# line_sensor.net
KiCad netlist of a schematic drawn in EAGLE
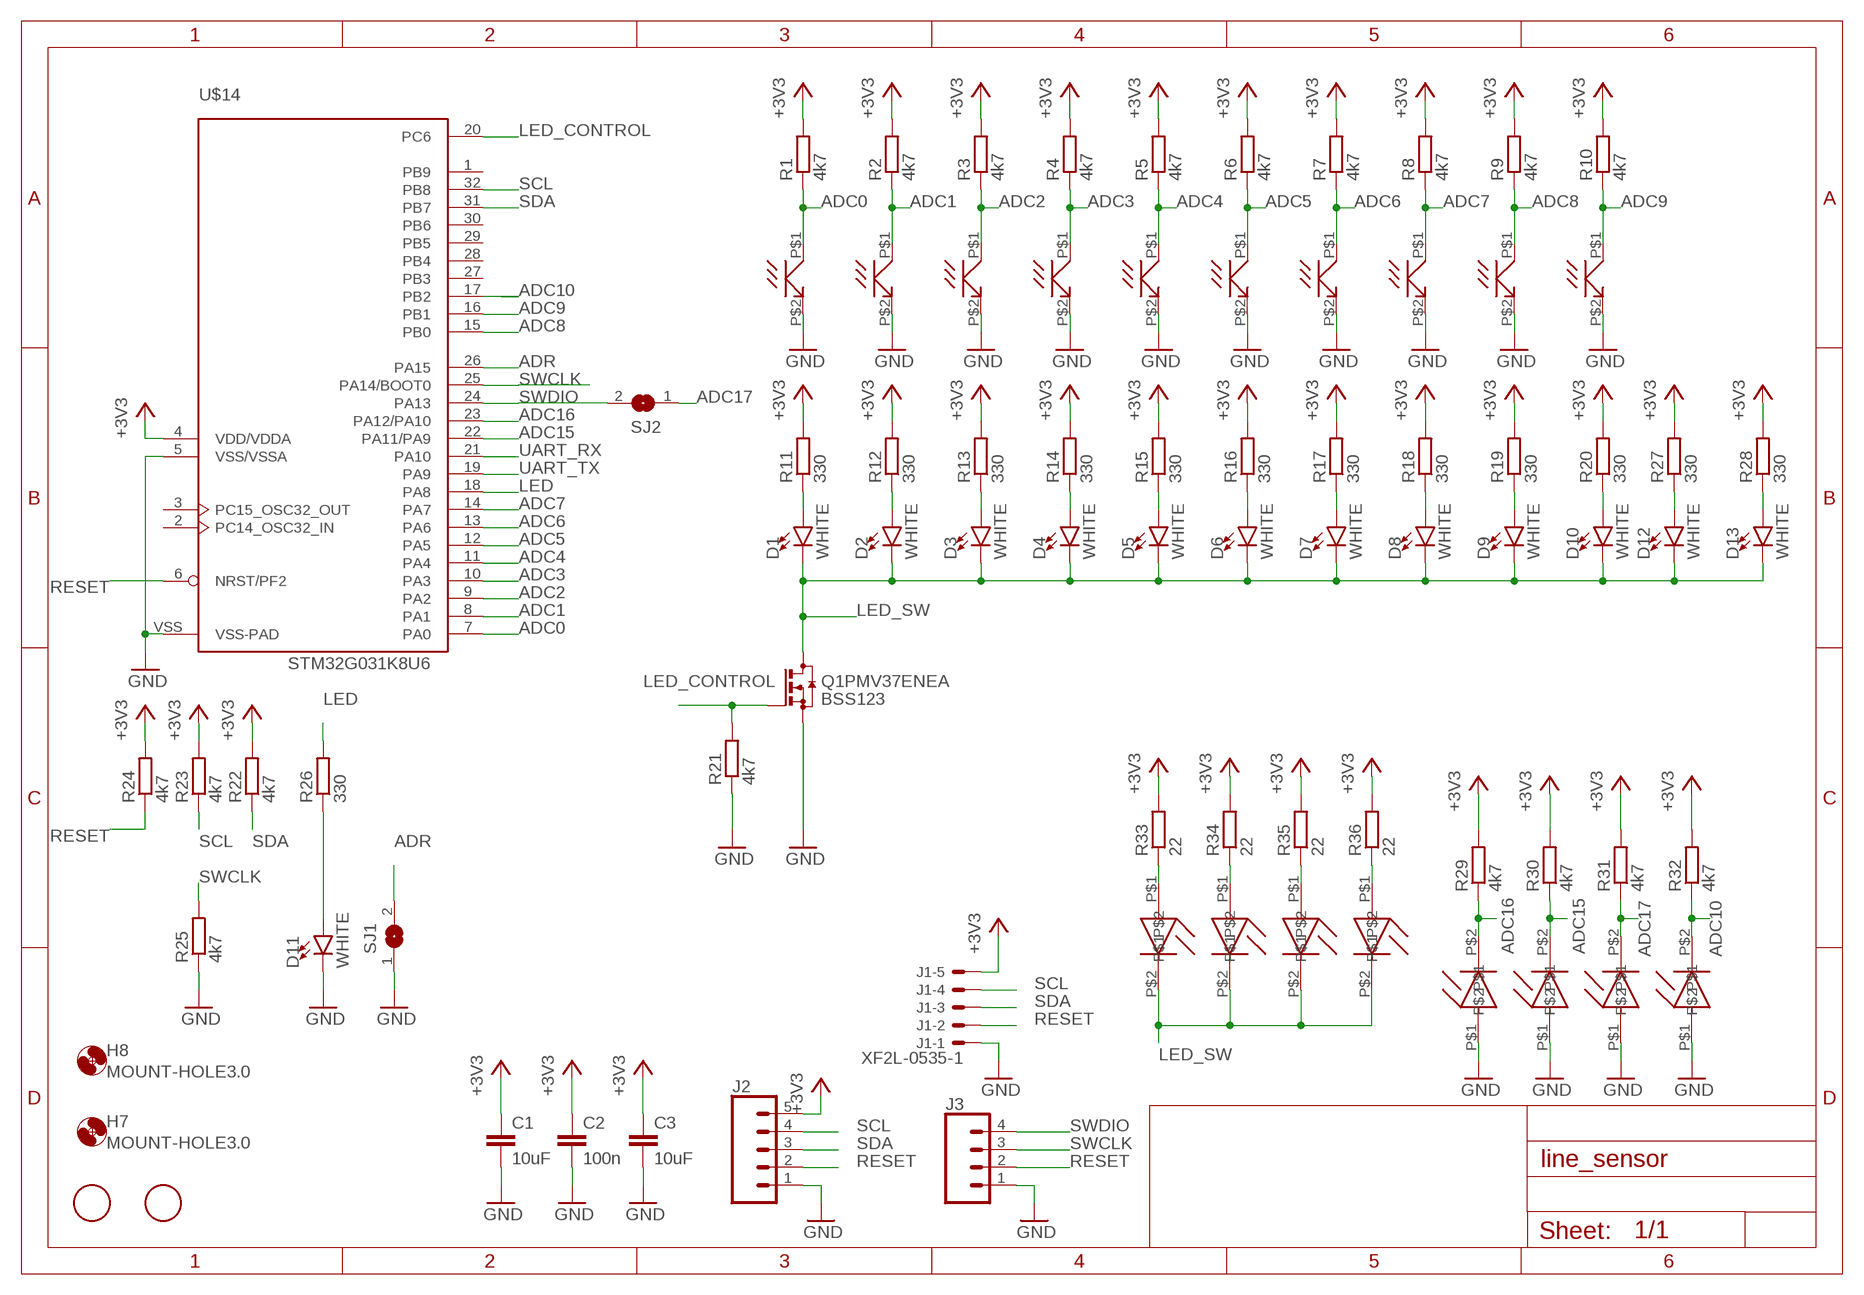
[diagram p0: schematic, sheet 1]

(export (version "E")
  (design (tool "Eeschema 10.0.6"))
  (components
    (comp (ref "C1")
      (value "10uF")
      (footprint "eagle-import:C0805K")
      (libsource (lib "eagle-import") (part "C-EUC0805K"))
    )
    (comp (ref "C2")
      (value "100n")
      (footprint "eagle-import:C0805K")
      (libsource (lib "eagle-import") (part "C-EUC0805K"))
    )
    (comp (ref "C3")
      (value "10uF")
      (footprint "eagle-import:C0805K")
      (libsource (lib "eagle-import") (part "C-EUC0805K"))
    )
    (comp (ref "D1")
      (value "WHITE")
      (footprint "eagle-import:LED-1206")
      (libsource (lib "eagle-import") (part "LED-WHITE1206"))
    )
    (comp (ref "D2")
      (value "WHITE")
      (footprint "eagle-import:LED-1206")
      (libsource (lib "eagle-import") (part "LED-WHITE1206"))
    )
    (comp (ref "D3")
      (value "WHITE")
      (footprint "eagle-import:LED-1206")
      (libsource (lib "eagle-import") (part "LED-WHITE1206"))
    )
    (comp (ref "D4")
      (value "WHITE")
      (footprint "eagle-import:LED-1206")
      (libsource (lib "eagle-import") (part "LED-WHITE1206"))
    )
    (comp (ref "D5")
      (value "WHITE")
      (footprint "eagle-import:LED-1206")
      (libsource (lib "eagle-import") (part "LED-WHITE1206"))
    )
    (comp (ref "D6")
      (value "WHITE")
      (footprint "eagle-import:LED-1206")
      (libsource (lib "eagle-import") (part "LED-WHITE1206"))
    )
    (comp (ref "D7")
      (value "WHITE")
      (footprint "eagle-import:LED-1206")
      (libsource (lib "eagle-import") (part "LED-WHITE1206"))
    )
    (comp (ref "D8")
      (value "WHITE")
      (footprint "eagle-import:LED-1206")
      (libsource (lib "eagle-import") (part "LED-WHITE1206"))
    )
    (comp (ref "D9")
      (value "WHITE")
      (footprint "eagle-import:LED-1206")
      (libsource (lib "eagle-import") (part "LED-WHITE1206"))
    )
    (comp (ref "D10")
      (value "WHITE")
      (footprint "eagle-import:LED-1206")
      (libsource (lib "eagle-import") (part "LED-WHITE1206"))
    )
    (comp (ref "D11")
      (value "WHITE")
      (footprint "eagle-import:LED-1206")
      (libsource (lib "eagle-import") (part "LED-WHITE1206"))
    )
    (comp (ref "D12")
      (value "WHITE")
      (footprint "eagle-import:LED-1206")
      (libsource (lib "eagle-import") (part "LED-WHITE1206"))
    )
    (comp (ref "D13")
      (value "WHITE")
      (footprint "eagle-import:LED-1206")
      (libsource (lib "eagle-import") (part "LED-WHITE1206"))
    )
    (comp (ref "H7")
      (value "MOUNT-HOLE3.0")
      (footprint "eagle-import:3,0")
      (libsource (lib "eagle-import") (part "MOUNT-HOLE3.0"))
    )
    (comp (ref "H8")
      (value "MOUNT-HOLE3.0")
      (footprint "eagle-import:3,0")
      (libsource (lib "eagle-import") (part "MOUNT-HOLE3.0"))
    )
    (comp (ref "J1")
      (value "XF2L-0535-1")
      (footprint "eagle-import:XF2L-0535-1")
      (fields (field (name "MPN") "XF2L-0535-1A"))
      (libsource (lib "eagle-import") (part "XF2-05?35-1L"))
    )
    (comp (ref "J2")
      (value "CONN_05")
      (footprint "eagle-import:1X05")
      (libsource (lib "eagle-import") (part "CONN_05"))
    )
    (comp (ref "J3")
      (value "CONN_04LOCK")
      (footprint "eagle-import:1X04_LOCK")
      (libsource (lib "eagle-import") (part "CONN_04LOCK"))
    )
    (comp (ref "Q1PMV37ENEA")
      (value "BSS123")
      (footprint "eagle-import:SOT23")
      (libsource (lib "eagle-import") (part "BSS123"))
    )
    (comp (ref "R1")
      (value "4k7")
      (footprint "eagle-import:M0805")
      (libsource (lib "eagle-import") (part "R-EU_M0805"))
    )
    (comp (ref "R2")
      (value "4k7")
      (footprint "eagle-import:M0805")
      (libsource (lib "eagle-import") (part "R-EU_M0805"))
    )
    (comp (ref "R3")
      (value "4k7")
      (footprint "eagle-import:M0805")
      (libsource (lib "eagle-import") (part "R-EU_M0805"))
    )
    (comp (ref "R4")
      (value "4k7")
      (footprint "eagle-import:M0805")
      (libsource (lib "eagle-import") (part "R-EU_M0805"))
    )
    (comp (ref "R5")
      (value "4k7")
      (footprint "eagle-import:M0805")
      (libsource (lib "eagle-import") (part "R-EU_M0805"))
    )
    (comp (ref "R6")
      (value "4k7")
      (footprint "eagle-import:M0805")
      (libsource (lib "eagle-import") (part "R-EU_M0805"))
    )
    (comp (ref "R7")
      (value "4k7")
      (footprint "eagle-import:M0805")
      (libsource (lib "eagle-import") (part "R-EU_M0805"))
    )
    (comp (ref "R8")
      (value "4k7")
      (footprint "eagle-import:M0805")
      (libsource (lib "eagle-import") (part "R-EU_M0805"))
    )
    (comp (ref "R9")
      (value "4k7")
      (footprint "eagle-import:M0805")
      (libsource (lib "eagle-import") (part "R-EU_M0805"))
    )
    (comp (ref "R10")
      (value "4k7")
      (footprint "eagle-import:M0805")
      (libsource (lib "eagle-import") (part "R-EU_M0805"))
    )
    (comp (ref "R11")
      (value "330")
      (footprint "eagle-import:M0805")
      (libsource (lib "eagle-import") (part "R-EU_M0805"))
    )
    (comp (ref "R12")
      (value "330")
      (footprint "eagle-import:M0805")
      (libsource (lib "eagle-import") (part "R-EU_M0805"))
    )
    (comp (ref "R13")
      (value "330")
      (footprint "eagle-import:M0805")
      (libsource (lib "eagle-import") (part "R-EU_M0805"))
    )
    (comp (ref "R14")
      (value "330")
      (footprint "eagle-import:M0805")
      (libsource (lib "eagle-import") (part "R-EU_M0805"))
    )
    (comp (ref "R15")
      (value "330")
      (footprint "eagle-import:M0805")
      (libsource (lib "eagle-import") (part "R-EU_M0805"))
    )
    (comp (ref "R16")
      (value "330")
      (footprint "eagle-import:M0805")
      (libsource (lib "eagle-import") (part "R-EU_M0805"))
    )
    (comp (ref "R17")
      (value "330")
      (footprint "eagle-import:M0805")
      (libsource (lib "eagle-import") (part "R-EU_M0805"))
    )
    (comp (ref "R18")
      (value "330")
      (footprint "eagle-import:M0805")
      (libsource (lib "eagle-import") (part "R-EU_M0805"))
    )
    (comp (ref "R19")
      (value "330")
      (footprint "eagle-import:M0805")
      (libsource (lib "eagle-import") (part "R-EU_M0805"))
    )
    (comp (ref "R20")
      (value "330")
      (footprint "eagle-import:M0805")
      (libsource (lib "eagle-import") (part "R-EU_M0805"))
    )
    (comp (ref "R21")
      (value "4k7")
      (footprint "eagle-import:M0805")
      (libsource (lib "eagle-import") (part "R-EU_M0805"))
    )
    (comp (ref "R22")
      (value "4k7")
      (footprint "eagle-import:M0805")
      (libsource (lib "eagle-import") (part "R-EU_M0805"))
    )
    (comp (ref "R23")
      (value "4k7")
      (footprint "eagle-import:M0805")
      (libsource (lib "eagle-import") (part "R-EU_M0805"))
    )
    (comp (ref "R24")
      (value "4k7")
      (footprint "eagle-import:M0805")
      (libsource (lib "eagle-import") (part "R-EU_M0805"))
    )
    (comp (ref "R25")
      (value "4k7")
      (footprint "eagle-import:M0805")
      (libsource (lib "eagle-import") (part "R-EU_M0805"))
    )
    (comp (ref "R26")
      (value "330")
      (footprint "eagle-import:M0805")
      (libsource (lib "eagle-import") (part "R-EU_M0805"))
    )
    (comp (ref "R27")
      (value "330")
      (footprint "eagle-import:M0805")
      (libsource (lib "eagle-import") (part "R-EU_M0805"))
    )
    (comp (ref "R28")
      (value "330")
      (footprint "eagle-import:M0805")
      (libsource (lib "eagle-import") (part "R-EU_M0805"))
    )
    (comp (ref "R29")
      (value "4k7")
      (footprint "eagle-import:M0805")
      (libsource (lib "eagle-import") (part "R-EU_M0805"))
    )
    (comp (ref "R30")
      (value "4k7")
      (footprint "eagle-import:M0805")
      (libsource (lib "eagle-import") (part "R-EU_M0805"))
    )
    (comp (ref "R31")
      (value "4k7")
      (footprint "eagle-import:M0805")
      (libsource (lib "eagle-import") (part "R-EU_M0805"))
    )
    (comp (ref "R32")
      (value "4k7")
      (footprint "eagle-import:M0805")
      (libsource (lib "eagle-import") (part "R-EU_M0805"))
    )
    (comp (ref "R33")
      (value "22")
      (footprint "eagle-import:M0805")
      (libsource (lib "eagle-import") (part "R-EU_M0805"))
    )
    (comp (ref "R34")
      (value "22")
      (footprint "eagle-import:M0805")
      (libsource (lib "eagle-import") (part "R-EU_M0805"))
    )
    (comp (ref "R35")
      (value "22")
      (footprint "eagle-import:M0805")
      (libsource (lib "eagle-import") (part "R-EU_M0805"))
    )
    (comp (ref "R36")
      (value "22")
      (footprint "eagle-import:M0805")
      (libsource (lib "eagle-import") (part "R-EU_M0805"))
    )
    (comp (ref "SJ1") (value "SJ") (footprint "eagle-import:SJ") (libsource (lib "eagle-import") (part "SJ")))
    (comp (ref "SJ2") (value "SJ") (footprint "eagle-import:SJ") (libsource (lib "eagle-import") (part "SJ")))
    (comp (ref "U$1")
      (value "SFH3710")
      (footprint "eagle-import:SFH710")
      (libsource (lib "eagle-import") (part "SFH3710"))
    )
    (comp (ref "U$2")
      (value "SFH3710")
      (footprint "eagle-import:SFH710")
      (libsource (lib "eagle-import") (part "SFH3710"))
    )
    (comp (ref "U$3")
      (value "SFH3710")
      (footprint "eagle-import:SFH710")
      (libsource (lib "eagle-import") (part "SFH3710"))
    )
    (comp (ref "U$4")
      (value "SFH3710")
      (footprint "eagle-import:SFH710")
      (libsource (lib "eagle-import") (part "SFH3710"))
    )
    (comp (ref "U$5")
      (value "SFH3710")
      (footprint "eagle-import:SFH710")
      (libsource (lib "eagle-import") (part "SFH3710"))
    )
    (comp (ref "U$6")
      (value "SFH3710")
      (footprint "eagle-import:SFH710")
      (libsource (lib "eagle-import") (part "SFH3710"))
    )
    (comp (ref "U$7")
      (value "SFH3710")
      (footprint "eagle-import:SFH710")
      (libsource (lib "eagle-import") (part "SFH3710"))
    )
    (comp (ref "U$8")
      (value "SFH3710")
      (footprint "eagle-import:SFH710")
      (libsource (lib "eagle-import") (part "SFH3710"))
    )
    (comp (ref "U$9")
      (value "SFH3710")
      (footprint "eagle-import:SFH710")
      (libsource (lib "eagle-import") (part "SFH3710"))
    )
    (comp (ref "U$10")
      (value "SFH3710")
      (footprint "eagle-import:SFH710")
      (libsource (lib "eagle-import") (part "SFH3710"))
    )
    (comp (ref "U$11")
      (value "LED_5MM_AXIAL")
      (footprint "eagle-import:LED_5MM_AXIAL")
      (libsource (lib "eagle-import") (part "LED_5MM_AXIAL"))
    )
    (comp (ref "U$12")
      (value "FIDUCIAL")
      (footprint "eagle-import:FIDUCIAL_1MM")
      (libsource (lib "eagle-import") (part "FIDUCIAL"))
    )
    (comp (ref "U$13")
      (value "FIDUCIAL")
      (footprint "eagle-import:FIDUCIAL_1MM")
      (libsource (lib "eagle-import") (part "FIDUCIAL"))
    )
    (comp (ref "U$14")
      (value "STM32G031K8U6")
      (footprint "eagle-import:UFQFPN32")
      (libsource (lib "eagle-import") (part "STM32G031K8U6"))
    )
    (comp (ref "U$15")
      (value "LED_5MM_AXIAL")
      (footprint "eagle-import:LED_5MM_AXIAL")
      (libsource (lib "eagle-import") (part "LED_5MM_AXIAL"))
    )
    (comp (ref "U$16")
      (value "LED_5MM_AXIAL")
      (footprint "eagle-import:LED_5MM_AXIAL")
      (libsource (lib "eagle-import") (part "LED_5MM_AXIAL"))
    )
    (comp (ref "U$17")
      (value "LED_5MM_AXIAL")
      (footprint "eagle-import:LED_5MM_AXIAL")
      (libsource (lib "eagle-import") (part "LED_5MM_AXIAL"))
    )
    (comp (ref "U$18")
      (value "LED_5MM_AXIAL")
      (footprint "eagle-import:LED_5MM_AXIAL")
      (libsource (lib "eagle-import") (part "LED_5MM_AXIAL"))
    )
    (comp (ref "U$19")
      (value "LED_5MM_AXIAL")
      (footprint "eagle-import:LED_5MM_AXIAL")
      (libsource (lib "eagle-import") (part "LED_5MM_AXIAL"))
    )
    (comp (ref "U$20")
      (value "LED_5MM_AXIAL")
      (footprint "eagle-import:LED_5MM_AXIAL")
      (libsource (lib "eagle-import") (part "LED_5MM_AXIAL"))
    )
    (comp (ref "U$21")
      (value "LED_5MM_AXIAL")
      (footprint "eagle-import:LED_5MM_AXIAL")
      (libsource (lib "eagle-import") (part "LED_5MM_AXIAL"))
    )
  )
  (nets
    (net (code "1") (name "+3V3") (class "Default")
      (node (ref "C1") (pin "1") (pinfunction "1_1") (pintype "passive"))
      (node (ref "C2") (pin "1") (pinfunction "1_1") (pintype "passive"))
      (node (ref "C3") (pin "1") (pinfunction "1_1") (pintype "passive"))
      (node (ref "J1") (pin "5") (pinfunction "MS_5") (pintype "passive"))
      (node (ref "J2") (pin "5") (pinfunction "5_5") (pintype "passive"))
      (node (ref "R1") (pin "2") (pinfunction "2_2") (pintype "passive"))
      (node (ref "R10") (pin "2") (pinfunction "2_2") (pintype "passive"))
      (node (ref "R11") (pin "2") (pinfunction "2_2") (pintype "passive"))
      (node (ref "R12") (pin "2") (pinfunction "2_2") (pintype "passive"))
      (node (ref "R13") (pin "2") (pinfunction "2_2") (pintype "passive"))
      (node (ref "R14") (pin "2") (pinfunction "2_2") (pintype "passive"))
      (node (ref "R15") (pin "2") (pinfunction "2_2") (pintype "passive"))
      (node (ref "R16") (pin "2") (pinfunction "2_2") (pintype "passive"))
      (node (ref "R17") (pin "2") (pinfunction "2_2") (pintype "passive"))
      (node (ref "R18") (pin "2") (pinfunction "2_2") (pintype "passive"))
      (node (ref "R19") (pin "2") (pinfunction "2_2") (pintype "passive"))
      (node (ref "R2") (pin "2") (pinfunction "2_2") (pintype "passive"))
      (node (ref "R20") (pin "2") (pinfunction "2_2") (pintype "passive"))
      (node (ref "R22") (pin "2") (pinfunction "2_2") (pintype "passive"))
      (node (ref "R23") (pin "2") (pinfunction "2_2") (pintype "passive"))
      (node (ref "R24") (pin "2") (pinfunction "2_2") (pintype "passive"))
      (node (ref "R27") (pin "2") (pinfunction "2_2") (pintype "passive"))
      (node (ref "R28") (pin "2") (pinfunction "2_2") (pintype "passive"))
      (node (ref "R29") (pin "2") (pinfunction "2_2") (pintype "passive"))
      (node (ref "R3") (pin "2") (pinfunction "2_2") (pintype "passive"))
      (node (ref "R30") (pin "2") (pinfunction "2_2") (pintype "passive"))
      (node (ref "R31") (pin "2") (pinfunction "2_2") (pintype "passive"))
      (node (ref "R32") (pin "2") (pinfunction "2_2") (pintype "passive"))
      (node (ref "R33") (pin "2") (pinfunction "2_2") (pintype "passive"))
      (node (ref "R34") (pin "2") (pinfunction "2_2") (pintype "passive"))
      (node (ref "R35") (pin "2") (pinfunction "2_2") (pintype "passive"))
      (node (ref "R36") (pin "2") (pinfunction "2_2") (pintype "passive"))
      (node (ref "R4") (pin "2") (pinfunction "2_2") (pintype "passive"))
      (node (ref "R5") (pin "2") (pinfunction "2_2") (pintype "passive"))
      (node (ref "R6") (pin "2") (pinfunction "2_2") (pintype "passive"))
      (node (ref "R7") (pin "2") (pinfunction "2_2") (pintype "passive"))
      (node (ref "R8") (pin "2") (pinfunction "2_2") (pintype "passive"))
      (node (ref "R9") (pin "2") (pinfunction "2_2") (pintype "passive"))
      (node (ref "U$14") (pin "4") (pinfunction "VDD/VDDA_4") (pintype "power_in"))
    )
    (net (code "2") (name "/ADC0") (class "Default")
      (node (ref "R1") (pin "1") (pinfunction "1_1") (pintype "passive"))
      (node (ref "U$1") (pin "P$1") (pinfunction "C_P$1") (pintype "bidirectional"))
      (node (ref "U$14") (pin "7") (pinfunction "PA0_7") (pintype "bidirectional"))
    )
    (net (code "3") (name "/ADC1") (class "Default")
      (node (ref "R2") (pin "1") (pinfunction "1_1") (pintype "passive"))
      (node (ref "U$14") (pin "8") (pinfunction "PA1_8") (pintype "bidirectional"))
      (node (ref "U$2") (pin "P$1") (pinfunction "C_P$1") (pintype "bidirectional"))
    )
    (net (code "4") (name "/ADC2") (class "Default")
      (node (ref "R3") (pin "1") (pinfunction "1_1") (pintype "passive"))
      (node (ref "U$14") (pin "9") (pinfunction "PA2_9") (pintype "bidirectional"))
      (node (ref "U$3") (pin "P$1") (pinfunction "C_P$1") (pintype "bidirectional"))
    )
    (net (code "5") (name "/ADC3") (class "Default")
      (node (ref "R4") (pin "1") (pinfunction "1_1") (pintype "passive"))
      (node (ref "U$14") (pin "10") (pinfunction "PA3_10") (pintype "bidirectional"))
      (node (ref "U$4") (pin "P$1") (pinfunction "C_P$1") (pintype "bidirectional"))
    )
    (net (code "6") (name "/ADC4") (class "Default")
      (node (ref "R5") (pin "1") (pinfunction "1_1") (pintype "passive"))
      (node (ref "U$14") (pin "11") (pinfunction "PA4_11") (pintype "bidirectional"))
      (node (ref "U$5") (pin "P$1") (pinfunction "C_P$1") (pintype "bidirectional"))
    )
    (net (code "7") (name "/ADC5") (class "Default")
      (node (ref "R6") (pin "1") (pinfunction "1_1") (pintype "passive"))
      (node (ref "U$14") (pin "12") (pinfunction "PA5_12") (pintype "bidirectional"))
      (node (ref "U$6") (pin "P$1") (pinfunction "C_P$1") (pintype "bidirectional"))
    )
    (net (code "8") (name "/ADC6") (class "Default")
      (node (ref "R7") (pin "1") (pinfunction "1_1") (pintype "passive"))
      (node (ref "U$14") (pin "13") (pinfunction "PA6_13") (pintype "bidirectional"))
      (node (ref "U$7") (pin "P$1") (pinfunction "C_P$1") (pintype "bidirectional"))
    )
    (net (code "9") (name "/ADC7") (class "Default")
      (node (ref "R8") (pin "1") (pinfunction "1_1") (pintype "passive"))
      (node (ref "U$14") (pin "14") (pinfunction "PA7_14") (pintype "bidirectional"))
      (node (ref "U$8") (pin "P$1") (pinfunction "C_P$1") (pintype "bidirectional"))
    )
    (net (code "10") (name "/ADC8") (class "Default")
      (node (ref "R9") (pin "1") (pinfunction "1_1") (pintype "passive"))
      (node (ref "U$14") (pin "15") (pinfunction "PB0_15") (pintype "bidirectional"))
      (node (ref "U$9") (pin "P$1") (pinfunction "C_P$1") (pintype "bidirectional"))
    )
    (net (code "11") (name "/ADC9") (class "Default")
      (node (ref "R10") (pin "1") (pinfunction "1_1") (pintype "passive"))
      (node (ref "U$10") (pin "P$1") (pinfunction "C_P$1") (pintype "bidirectional"))
      (node (ref "U$14") (pin "16") (pinfunction "PB1_16") (pintype "bidirectional"))
    )
    (net (code "12") (name "/ADC10") (class "Default")
      (node (ref "R32") (pin "1") (pinfunction "1_1") (pintype "passive"))
      (node (ref "U$14") (pin "17") (pinfunction "PB2_17") (pintype "bidirectional"))
      (node (ref "U$21") (pin "P$2") (pinfunction "P$2_P$2") (pintype "bidirectional"))
    )
    (net (code "13") (name "/ADC15") (class "Default")
      (node (ref "R30") (pin "1") (pinfunction "1_1") (pintype "passive"))
      (node (ref "U$14") (pin "22") (pinfunction "PA11/PA9_22") (pintype "bidirectional"))
      (node (ref "U$17") (pin "P$2") (pinfunction "P$2_P$2") (pintype "bidirectional"))
    )
    (net (code "14") (name "/ADC16") (class "Default")
      (node (ref "R29") (pin "1") (pinfunction "1_1") (pintype "passive"))
      (node (ref "U$14") (pin "23") (pinfunction "PA12/PA10_23") (pintype "bidirectional"))
      (node (ref "U$15") (pin "P$2") (pinfunction "P$2_P$2") (pintype "bidirectional"))
    )
    (net (code "15") (name "/ADC17") (class "Default")
      (node (ref "R31") (pin "1") (pinfunction "1_1") (pintype "passive"))
      (node (ref "SJ2") (pin "1") (pinfunction "1_1") (pintype "passive"))
      (node (ref "U$19") (pin "P$2") (pinfunction "P$2_P$2") (pintype "bidirectional"))
    )
    (net (code "16") (name "/ADR") (class "Default")
      (node (ref "SJ1") (pin "2") (pinfunction "2_2") (pintype "passive"))
      (node (ref "U$14") (pin "26") (pinfunction "PA15_26") (pintype "bidirectional"))
    )
    (net (code "17") (name "/LED") (class "Default")
      (node (ref "R26") (pin "2") (pinfunction "2_2") (pintype "passive"))
      (node (ref "U$14") (pin "18") (pinfunction "PA8_18") (pintype "bidirectional"))
    )
    (net (code "18") (name "/LED_CONTROL") (class "Default")
      (node (ref "Q1PMV37ENEA") (pin "1") (pinfunction "G_1") (pintype "passive"))
      (node (ref "R21") (pin "2") (pinfunction "2_2") (pintype "passive"))
      (node (ref "U$14") (pin "20") (pinfunction "PC6_20") (pintype "bidirectional"))
    )
    (net (code "19") (name "/LED_SW") (class "Default")
      (node (ref "D1") (pin "C") (pinfunction "C_C") (pintype "passive"))
      (node (ref "D10") (pin "C") (pinfunction "C_C") (pintype "passive"))
      (node (ref "D12") (pin "C") (pinfunction "C_C") (pintype "passive"))
      (node (ref "D13") (pin "C") (pinfunction "C_C") (pintype "passive"))
      (node (ref "D2") (pin "C") (pinfunction "C_C") (pintype "passive"))
      (node (ref "D3") (pin "C") (pinfunction "C_C") (pintype "passive"))
      (node (ref "D4") (pin "C") (pinfunction "C_C") (pintype "passive"))
      (node (ref "D5") (pin "C") (pinfunction "C_C") (pintype "passive"))
      (node (ref "D6") (pin "C") (pinfunction "C_C") (pintype "passive"))
      (node (ref "D7") (pin "C") (pinfunction "C_C") (pintype "passive"))
      (node (ref "D8") (pin "C") (pinfunction "C_C") (pintype "passive"))
      (node (ref "D9") (pin "C") (pinfunction "C_C") (pintype "passive"))
      (node (ref "Q1PMV37ENEA") (pin "3") (pinfunction "D_3") (pintype "passive"))
      (node (ref "U$11") (pin "P$2") (pinfunction "P$2_P$2") (pintype "bidirectional"))
      (node (ref "U$16") (pin "P$2") (pinfunction "P$2_P$2") (pintype "bidirectional"))
      (node (ref "U$18") (pin "P$2") (pinfunction "P$2_P$2") (pintype "bidirectional"))
      (node (ref "U$20") (pin "P$2") (pinfunction "P$2_P$2") (pintype "bidirectional"))
    )
    (net (code "20") (name "/RESET") (class "Default")
      (node (ref "J1") (pin "2") (pinfunction "MS_2") (pintype "passive"))
      (node (ref "J2") (pin "2") (pinfunction "2_2") (pintype "passive"))
      (node (ref "J3") (pin "2") (pinfunction "2_2") (pintype "passive"))
      (node (ref "R24") (pin "1") (pinfunction "1_1") (pintype "passive"))
      (node (ref "U$14") (pin "6") (pinfunction "NRST/PF2_6") (pintype "bidirectional"))
    )
    (net (code "21") (name "/SCL") (class "Default")
      (node (ref "J1") (pin "4") (pinfunction "MS_4") (pintype "passive"))
      (node (ref "J2") (pin "4") (pinfunction "4_4") (pintype "passive"))
      (node (ref "R23") (pin "1") (pinfunction "1_1") (pintype "passive"))
      (node (ref "U$14") (pin "32") (pinfunction "PB8_32") (pintype "bidirectional"))
    )
    (net (code "22") (name "/SDA") (class "Default")
      (node (ref "J1") (pin "3") (pinfunction "MS_3") (pintype "passive"))
      (node (ref "J2") (pin "3") (pinfunction "3_3") (pintype "passive"))
      (node (ref "R22") (pin "1") (pinfunction "1_1") (pintype "passive"))
      (node (ref "U$14") (pin "31") (pinfunction "PB7_31") (pintype "bidirectional"))
    )
    (net (code "23") (name "/SWCLK") (class "Default")
      (node (ref "J3") (pin "3") (pinfunction "3_3") (pintype "passive"))
      (node (ref "R25") (pin "2") (pinfunction "2_2") (pintype "passive"))
      (node (ref "U$14") (pin "25") (pinfunction "PA14/BOOT0_25") (pintype "bidirectional"))
    )
    (net (code "24") (name "/SWDIO") (class "Default")
      (node (ref "J3") (pin "4") (pinfunction "4_4") (pintype "passive"))
      (node (ref "SJ2") (pin "2") (pinfunction "2_2") (pintype "passive"))
      (node (ref "U$14") (pin "24") (pinfunction "PA13_24") (pintype "bidirectional"))
    )
    (net (code "25") (name "/UART_RX") (class "Default")
      (node (ref "U$14") (pin "21") (pinfunction "PA10_21") (pintype "bidirectional"))
    )
    (net (code "26") (name "/UART_TX") (class "Default")
      (node (ref "U$14") (pin "19") (pinfunction "PA9_19") (pintype "bidirectional"))
    )
    (net (code "27") (name "GND") (class "Default")
      (node (ref "C1") (pin "2") (pinfunction "2_2") (pintype "passive"))
      (node (ref "C2") (pin "2") (pinfunction "2_2") (pintype "passive"))
      (node (ref "C3") (pin "2") (pinfunction "2_2") (pintype "passive"))
      (node (ref "D11") (pin "C") (pinfunction "C_C") (pintype "passive"))
      (node (ref "J1") (pin "1") (pinfunction "MSV_1") (pintype "passive"))
      (node (ref "J2") (pin "1") (pinfunction "1_1") (pintype "passive"))
      (node (ref "J3") (pin "1") (pinfunction "1_1") (pintype "passive"))
      (node (ref "Q1PMV37ENEA") (pin "2") (pinfunction "S_2") (pintype "passive"))
      (node (ref "R21") (pin "1") (pinfunction "1_1") (pintype "passive"))
      (node (ref "R25") (pin "1") (pinfunction "1_1") (pintype "passive"))
      (node (ref "SJ1") (pin "1") (pinfunction "1_1") (pintype "passive"))
      (node (ref "U$1") (pin "P$2") (pinfunction "E_P$2") (pintype "bidirectional"))
      (node (ref "U$10") (pin "P$2") (pinfunction "E_P$2") (pintype "bidirectional"))
      (node (ref "U$14") (pin "5") (pinfunction "VSS/VSSA_5") (pintype "power_in"))
      (node (ref "U$14") (pin "VSS") (pinfunction "VSS-PAD_VSS") (pintype "bidirectional"))
      (node (ref "U$15") (pin "P$1") (pinfunction "P$1_P$1") (pintype "bidirectional"))
      (node (ref "U$17") (pin "P$1") (pinfunction "P$1_P$1") (pintype "bidirectional"))
      (node (ref "U$19") (pin "P$1") (pinfunction "P$1_P$1") (pintype "bidirectional"))
      (node (ref "U$2") (pin "P$2") (pinfunction "E_P$2") (pintype "bidirectional"))
      (node (ref "U$21") (pin "P$1") (pinfunction "P$1_P$1") (pintype "bidirectional"))
      (node (ref "U$3") (pin "P$2") (pinfunction "E_P$2") (pintype "bidirectional"))
      (node (ref "U$4") (pin "P$2") (pinfunction "E_P$2") (pintype "bidirectional"))
      (node (ref "U$5") (pin "P$2") (pinfunction "E_P$2") (pintype "bidirectional"))
      (node (ref "U$6") (pin "P$2") (pinfunction "E_P$2") (pintype "bidirectional"))
      (node (ref "U$7") (pin "P$2") (pinfunction "E_P$2") (pintype "bidirectional"))
      (node (ref "U$8") (pin "P$2") (pinfunction "E_P$2") (pintype "bidirectional"))
      (node (ref "U$9") (pin "P$2") (pinfunction "E_P$2") (pintype "bidirectional"))
    )
    (net (code "28") (name "Net-(D1-PadA)") (class "Default")
      (node (ref "D1") (pin "A") (pinfunction "A_A") (pintype "passive"))
      (node (ref "R11") (pin "1") (pinfunction "1_1") (pintype "passive"))
    )
    (net (code "29") (name "Net-(D2-PadA)") (class "Default")
      (node (ref "D2") (pin "A") (pinfunction "A_A") (pintype "passive"))
      (node (ref "R12") (pin "1") (pinfunction "1_1") (pintype "passive"))
    )
    (net (code "30") (name "Net-(D3-PadA)") (class "Default")
      (node (ref "D3") (pin "A") (pinfunction "A_A") (pintype "passive"))
      (node (ref "R13") (pin "1") (pinfunction "1_1") (pintype "passive"))
    )
    (net (code "31") (name "Net-(D4-PadA)") (class "Default")
      (node (ref "D4") (pin "A") (pinfunction "A_A") (pintype "passive"))
      (node (ref "R14") (pin "1") (pinfunction "1_1") (pintype "passive"))
    )
    (net (code "32") (name "Net-(D5-PadA)") (class "Default")
      (node (ref "D5") (pin "A") (pinfunction "A_A") (pintype "passive"))
      (node (ref "R15") (pin "1") (pinfunction "1_1") (pintype "passive"))
    )
    (net (code "33") (name "Net-(D6-PadA)") (class "Default")
      (node (ref "D6") (pin "A") (pinfunction "A_A") (pintype "passive"))
      (node (ref "R16") (pin "1") (pinfunction "1_1") (pintype "passive"))
    )
    (net (code "34") (name "Net-(D7-PadA)") (class "Default")
      (node (ref "D7") (pin "A") (pinfunction "A_A") (pintype "passive"))
      (node (ref "R17") (pin "1") (pinfunction "1_1") (pintype "passive"))
    )
    (net (code "35") (name "Net-(D8-PadA)") (class "Default")
      (node (ref "D8") (pin "A") (pinfunction "A_A") (pintype "passive"))
      (node (ref "R18") (pin "1") (pinfunction "1_1") (pintype "passive"))
    )
    (net (code "36") (name "Net-(D9-PadA)") (class "Default")
      (node (ref "D9") (pin "A") (pinfunction "A_A") (pintype "passive"))
      (node (ref "R19") (pin "1") (pinfunction "1_1") (pintype "passive"))
    )
    (net (code "37") (name "Net-(D10-PadA)") (class "Default")
      (node (ref "D10") (pin "A") (pinfunction "A_A") (pintype "passive"))
      (node (ref "R20") (pin "1") (pinfunction "1_1") (pintype "passive"))
    )
    (net (code "38") (name "Net-(D11-PadA)") (class "Default")
      (node (ref "D11") (pin "A") (pinfunction "A_A") (pintype "passive"))
      (node (ref "R26") (pin "1") (pinfunction "1_1") (pintype "passive"))
    )
    (net (code "39") (name "Net-(D12-PadA)") (class "Default")
      (node (ref "D12") (pin "A") (pinfunction "A_A") (pintype "passive"))
      (node (ref "R27") (pin "1") (pinfunction "1_1") (pintype "passive"))
    )
    (net (code "40") (name "Net-(D13-PadA)") (class "Default")
      (node (ref "D13") (pin "A") (pinfunction "A_A") (pintype "passive"))
      (node (ref "R28") (pin "1") (pinfunction "1_1") (pintype "passive"))
    )
    (net (code "41") (name "Net-(R33-Pad1)") (class "Default")
      (node (ref "R33") (pin "1") (pinfunction "1_1") (pintype "passive"))
      (node (ref "U$11") (pin "P$1") (pinfunction "P$1_P$1") (pintype "bidirectional"))
    )
    (net (code "42") (name "Net-(R34-Pad1)") (class "Default")
      (node (ref "R34") (pin "1") (pinfunction "1_1") (pintype "passive"))
      (node (ref "U$16") (pin "P$1") (pinfunction "P$1_P$1") (pintype "bidirectional"))
    )
    (net (code "43") (name "Net-(R35-Pad1)") (class "Default")
      (node (ref "R35") (pin "1") (pinfunction "1_1") (pintype "passive"))
      (node (ref "U$18") (pin "P$1") (pinfunction "P$1_P$1") (pintype "bidirectional"))
    )
    (net (code "44") (name "Net-(R36-Pad1)") (class "Default")
      (node (ref "R36") (pin "1") (pinfunction "1_1") (pintype "passive"))
      (node (ref "U$20") (pin "P$1") (pinfunction "P$1_P$1") (pintype "bidirectional"))
    )
    (net (code "45") (name "unconnected-(U$14-PB3-Pad27)") (class "Default")
      (node (ref "U$14") (pin "27") (pinfunction "PB3_27") (pintype "bidirectional"))
    )
    (net (code "46") (name "unconnected-(U$14-PB4-Pad28)") (class "Default")
      (node (ref "U$14") (pin "28") (pinfunction "PB4_28") (pintype "bidirectional"))
    )
    (net (code "47") (name "unconnected-(U$14-PB5-Pad29)") (class "Default")
      (node (ref "U$14") (pin "29") (pinfunction "PB5_29") (pintype "bidirectional"))
    )
    (net (code "48") (name "unconnected-(U$14-PB6-Pad30)") (class "Default")
      (node (ref "U$14") (pin "30") (pinfunction "PB6_30") (pintype "bidirectional"))
    )
    (net (code "49") (name "unconnected-(U$14-PB9-Pad1)") (class "Default")
      (node (ref "U$14") (pin "1") (pinfunction "PB9_1") (pintype "bidirectional"))
    )
    (net (code "50") (name "unconnected-(U$14-PC14_OSC32_IN-Pad2)") (class "Default")
      (node (ref "U$14") (pin "2") (pinfunction "PC14_OSC32_IN_2") (pintype "bidirectional"))
    )
    (net (code "51") (name "unconnected-(U$14-PC15_OSC32_OUT-Pad3)") (class "Default")
      (node (ref "U$14") (pin "3") (pinfunction "PC15_OSC32_OUT_3") (pintype "bidirectional"))
    )
  )
)
